# Guitar_Amp_0.net
KiCad netlist of a schematic drawn in Altium Designer
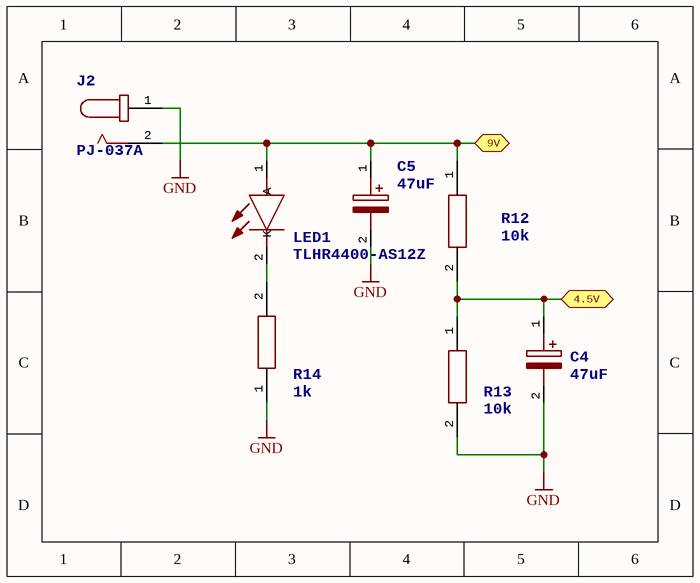
[diagram p0: Guitar Amp_0.SchDoc]

(export (version "E")
  (design (tool "Eeschema 10.0.6"))
  (components
    (comp (ref "C4")
      (value "47uF")
      (footprint "CAPPRD200W55D500H1200")
      (libsource (lib "SamacSys_Parts") (part "ECA-1CM470"))
    )
    (comp (ref "C5")
      (value "47uF")
      (footprint "CAPPRD200W55D500H1200")
      (libsource (lib "SamacSys_Parts") (part "ECA-1CM470"))
    )
    (comp (ref "J2")
      (value "PJ-037A")
      (footprint "CUI_PJ-037A")
      (description "2.0 mm Center Pin, 2.5 A, Right Angle, Through Hole, Dc Power Jack Connector Buy Part")
      (libsource (lib "PJ-037A") (part "PJ-037A"))
    )
    (comp (ref "LED1")
      (value "TLHR4400-AS12Z")
      (footprint "TLHR4400AS12Z")
      (description "Standard LEDs - Through Hole Red 13mcd; 3mm 612-625nm; 2V Typ   Source:  Datasheet")
      (libsource (lib "SamacSys_Parts") (part "TLHR4400-AS12Z"))
    )
    (comp (ref "R12")
      (value "10k")
      (footprint "RESAD1630W60L710D230")
      (description "Metal Film Resistors - Through Hole 1/4 WATT 10K OHM 5%   Source:  Datasheet")
      (libsource (lib "SamacSys_Parts") (part "MF1_4LCT52R103J"))
    )
    (comp (ref "R13")
      (value "10k")
      (footprint "RESAD1630W60L710D230")
      (description "Metal Film Resistors - Through Hole 1/4 WATT 10K OHM 5%   Source:  Datasheet")
      (libsource (lib "SamacSys_Parts") (part "MF1_4LCT52R103J"))
    )
    (comp (ref "R14")
      (value "1k")
      (footprint "RESAD1630W60L710D230")
      (description "Metal Film Resistors - Through Hole 1/4 WATT 10K OHM 5%   Source:  Datasheet")
      (libsource (lib "SamacSys_Parts") (part "MF1_4LCT52R103J"))
    )
  )
  (nets
    (net (code "1") (name "/4.5V") (class "Default")
      (node (ref "C4") (pin "1") (pinfunction "+_1") (pintype "passive"))
      (node (ref "R12") (pin "2") (pinfunction "2_2") (pintype "passive"))
      (node (ref "R13") (pin "1") (pinfunction "1_1") (pintype "passive"))
    )
    (net (code "2") (name "/9V") (class "Default")
      (node (ref "C5") (pin "1") (pinfunction "+_1") (pintype "passive"))
      (node (ref "J2") (pin "2") (pinfunction "2_2") (pintype "passive"))
      (node (ref "LED1") (pin "1") (pinfunction "A_1") (pintype "passive"))
      (node (ref "R12") (pin "1") (pinfunction "1_1") (pintype "passive"))
    )
    (net (code "3") (name "GND") (class "Default")
      (node (ref "C4") (pin "2") (pinfunction "-_2") (pintype "passive"))
      (node (ref "C5") (pin "2") (pinfunction "-_2") (pintype "passive"))
      (node (ref "J2") (pin "1") (pinfunction "1_1") (pintype "passive"))
      (node (ref "R13") (pin "2") (pinfunction "2_2") (pintype "passive"))
      (node (ref "R14") (pin "1") (pinfunction "1_1") (pintype "passive"))
    )
    (net (code "4") (name "Net-(LED1-K)") (class "Default")
      (node (ref "LED1") (pin "2") (pinfunction "K_2") (pintype "passive"))
      (node (ref "R14") (pin "2") (pinfunction "2_2") (pintype "passive"))
    )
  )
)
